# Main_schematic.net
KiCad netlist of a schematic drawn in EAGLE
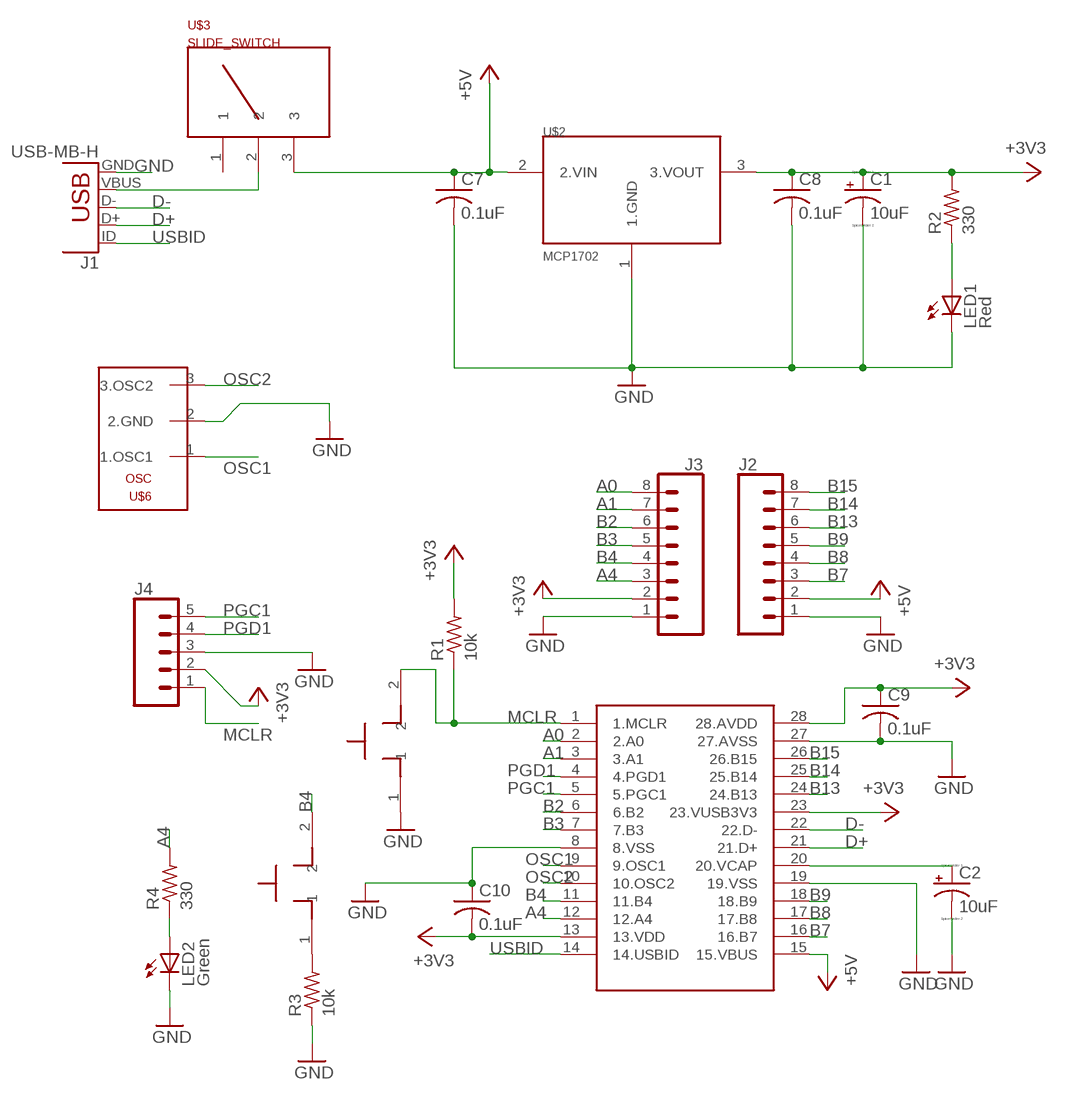
[diagram p0: schematic, sheet 1]

(export (version "E")
  (design (tool "Eeschema 10.0.6"))
  (components
    (comp (ref "C1")
      (value "10uF")
      (footprint "eagle-import:B45181B")
      (libsource (lib "eagle-import") (part "CPOL-USB45181B"))
    )
    (comp (ref "C2")
      (value "10uF")
      (footprint "eagle-import:B45181B")
      (libsource (lib "eagle-import") (part "CPOL-USB45181B"))
    )
    (comp (ref "C7")
      (value "0.1uF")
      (footprint "eagle-import:C025-024X044")
      (libsource (lib "eagle-import") (part "C-US025-024X044"))
    )
    (comp (ref "C8")
      (value "0.1uF")
      (footprint "eagle-import:C025-024X044")
      (libsource (lib "eagle-import") (part "C-US025-024X044"))
    )
    (comp (ref "C9")
      (value "0.1uF")
      (footprint "eagle-import:C025-024X044")
      (libsource (lib "eagle-import") (part "C-US025-024X044"))
    )
    (comp (ref "C10")
      (value "0.1uF")
      (footprint "eagle-import:C025-024X044")
      (libsource (lib "eagle-import") (part "C-US025-024X044"))
    )
    (comp (ref "J1")
      (value "USB-MB-H")
      (footprint "eagle-import:USB-MB-H")
      (libsource (lib "eagle-import") (part "USB-MB-H"))
    )
    (comp (ref "J2")
      (value "CONN_08\"")
      (footprint "eagle-import:1X08")
      (libsource (lib "eagle-import") (part "CONN_08{dblquote}"))
    )
    (comp (ref "J3")
      (value "CONN_08\"")
      (footprint "eagle-import:1X08")
      (libsource (lib "eagle-import") (part "CONN_08{dblquote}"))
    )
    (comp (ref "J4")
      (value "CONN_05")
      (footprint "eagle-import:1X05")
      (libsource (lib "eagle-import") (part "CONN_05"))
    )
    (comp (ref "LED1")
      (value "Red")
      (footprint "eagle-import:LED3MM")
      (libsource (lib "eagle-import") (part "LED3MM"))
    )
    (comp (ref "LED2")
      (value "Green")
      (footprint "eagle-import:LED3MM")
      (libsource (lib "eagle-import") (part "LED3MM"))
    )
    (comp (ref "R1")
      (value "10k")
      (footprint "eagle-import:0207_10")
      (libsource (lib "eagle-import") (part "R-US_0207/10"))
    )
    (comp (ref "R2")
      (value "330")
      (footprint "eagle-import:0207_10")
      (libsource (lib "eagle-import") (part "R-US_0207/10"))
    )
    (comp (ref "R3")
      (value "10k")
      (footprint "eagle-import:0207_10")
      (libsource (lib "eagle-import") (part "R-US_0207/10"))
    )
    (comp (ref "R4")
      (value "330")
      (footprint "eagle-import:0207_10")
      (libsource (lib "eagle-import") (part "R-US_0207/10"))
    )
    (comp (ref "U$1")
      (value "PIC32MX250F128B")
      (footprint "eagle-import:DIL28-3")
      (libsource (lib "eagle-import") (part "PIC32MX250F128B"))
    )
    (comp (ref "U$2")
      (value "MCP1702")
      (footprint "eagle-import:TO92")
      (libsource (lib "eagle-import") (part "MCP1702"))
    )
    (comp (ref "U$3")
      (value "SLIDE_SWITCH")
      (footprint "eagle-import:SLIDE_SWITCH")
      (libsource (lib "eagle-import") (part "SLIDE_SWITCH"))
    )
    (comp (ref "U$4") (value "PB") (footprint "eagle-import:PB") (libsource (lib "eagle-import") (part "PB")))
    (comp (ref "U$5") (value "PB") (footprint "eagle-import:PB") (libsource (lib "eagle-import") (part "PB")))
    (comp (ref "U$6")
      (value "OSC")
      (footprint "eagle-import:OSC")
      (libsource (lib "eagle-import") (part "OSC"))
    )
  )
  (nets
    (net (code "1") (name "+3V3") (class "Default")
      (node (ref "C1") (pin "+") (pinfunction "+_+") (pintype "passive"))
      (node (ref "C10") (pin "2") (pinfunction "2_2") (pintype "passive"))
      (node (ref "C8") (pin "1") (pinfunction "1_1") (pintype "passive"))
      (node (ref "C9") (pin "1") (pinfunction "1_1") (pintype "passive"))
      (node (ref "J3") (pin "2") (pinfunction "2_2") (pintype "passive"))
      (node (ref "J4") (pin "2") (pinfunction "2_2") (pintype "passive"))
      (node (ref "R1") (pin "2") (pinfunction "2_2") (pintype "passive"))
      (node (ref "R2") (pin "2") (pinfunction "2_2") (pintype "passive"))
      (node (ref "U$1") (pin "13") (pinfunction "13.VDD_13") (pintype "bidirectional"))
      (node (ref "U$1") (pin "23") (pinfunction "23.VUSB3V3_23") (pintype "bidirectional"))
      (node (ref "U$1") (pin "28") (pinfunction "28.AVDD_28") (pintype "bidirectional"))
      (node (ref "U$2") (pin "3") (pinfunction "3.VOUT_3") (pintype "bidirectional"))
    )
    (net (code "2") (name "+5V") (class "Default")
      (node (ref "C7") (pin "1") (pinfunction "1_1") (pintype "passive"))
      (node (ref "J2") (pin "2") (pinfunction "2_2") (pintype "passive"))
      (node (ref "U$1") (pin "15") (pinfunction "15.VBUS_15") (pintype "bidirectional"))
      (node (ref "U$2") (pin "2") (pinfunction "2.VIN_2") (pintype "bidirectional"))
      (node (ref "U$3") (pin "3") (pinfunction "3_3") (pintype "bidirectional"))
    )
    (net (code "3") (name "/A0") (class "Default")
      (node (ref "J3") (pin "8") (pinfunction "8_8") (pintype "passive"))
      (node (ref "U$1") (pin "2") (pinfunction "2.A0_2") (pintype "bidirectional"))
    )
    (net (code "4") (name "/A1") (class "Default")
      (node (ref "J3") (pin "7") (pinfunction "7_7") (pintype "passive"))
      (node (ref "U$1") (pin "3") (pinfunction "3.A1_3") (pintype "bidirectional"))
    )
    (net (code "5") (name "/A4") (class "Default")
      (node (ref "J3") (pin "3") (pinfunction "3_3") (pintype "passive"))
      (node (ref "R4") (pin "2") (pinfunction "2_2") (pintype "passive"))
      (node (ref "U$1") (pin "12") (pinfunction "12.A4_12") (pintype "bidirectional"))
    )
    (net (code "6") (name "/B2") (class "Default")
      (node (ref "J3") (pin "6") (pinfunction "6_6") (pintype "passive"))
      (node (ref "U$1") (pin "6") (pinfunction "6.B2_6") (pintype "bidirectional"))
    )
    (net (code "7") (name "/B3") (class "Default")
      (node (ref "J3") (pin "5") (pinfunction "5_5") (pintype "passive"))
      (node (ref "U$1") (pin "7") (pinfunction "7.B3_7") (pintype "bidirectional"))
    )
    (net (code "8") (name "/B4") (class "Default")
      (node (ref "J3") (pin "4") (pinfunction "4_4") (pintype "passive"))
      (node (ref "U$1") (pin "11") (pinfunction "11.B4_11") (pintype "bidirectional"))
      (node (ref "U$5") (pin "2") (pinfunction "2_2") (pintype "bidirectional"))
    )
    (net (code "9") (name "/B7") (class "Default")
      (node (ref "J2") (pin "3") (pinfunction "3_3") (pintype "passive"))
      (node (ref "U$1") (pin "16") (pinfunction "16.B7_16") (pintype "bidirectional"))
    )
    (net (code "10") (name "/B8") (class "Default")
      (node (ref "J2") (pin "4") (pinfunction "4_4") (pintype "passive"))
      (node (ref "U$1") (pin "17") (pinfunction "17.B8_17") (pintype "bidirectional"))
    )
    (net (code "11") (name "/B9") (class "Default")
      (node (ref "J2") (pin "5") (pinfunction "5_5") (pintype "passive"))
      (node (ref "U$1") (pin "18") (pinfunction "18.B9_18") (pintype "bidirectional"))
    )
    (net (code "12") (name "/B13") (class "Default")
      (node (ref "J2") (pin "6") (pinfunction "6_6") (pintype "passive"))
      (node (ref "U$1") (pin "24") (pinfunction "24.B13_24") (pintype "bidirectional"))
    )
    (net (code "13") (name "/B14") (class "Default")
      (node (ref "J2") (pin "7") (pinfunction "7_7") (pintype "passive"))
      (node (ref "U$1") (pin "25") (pinfunction "25.B14_25") (pintype "bidirectional"))
    )
    (net (code "14") (name "/B15") (class "Default")
      (node (ref "J2") (pin "8") (pinfunction "8_8") (pintype "passive"))
      (node (ref "U$1") (pin "26") (pinfunction "26.B15_26") (pintype "bidirectional"))
    )
    (net (code "15") (name "/D+") (class "Default")
      (node (ref "J1") (pin "D+") (pinfunction "D+_D+") (pintype "bidirectional"))
      (node (ref "U$1") (pin "21") (pinfunction "21.D+_21") (pintype "bidirectional"))
    )
    (net (code "16") (name "/D-") (class "Default")
      (node (ref "J1") (pin "D-") (pinfunction "D-_D-") (pintype "bidirectional"))
      (node (ref "U$1") (pin "22") (pinfunction "22.D-_22") (pintype "bidirectional"))
    )
    (net (code "17") (name "/MCLR") (class "Default")
      (node (ref "J4") (pin "1") (pinfunction "1_1") (pintype "passive"))
      (node (ref "R1") (pin "1") (pinfunction "1_1") (pintype "passive"))
      (node (ref "U$1") (pin "1") (pinfunction "1.MCLR_1") (pintype "bidirectional"))
      (node (ref "U$4") (pin "2") (pinfunction "2_2") (pintype "bidirectional"))
    )
    (net (code "18") (name "/OSC1") (class "Default")
      (node (ref "U$1") (pin "9") (pinfunction "9.OSC1_9") (pintype "bidirectional"))
      (node (ref "U$6") (pin "1") (pinfunction "1.OSC1_1") (pintype "bidirectional"))
    )
    (net (code "19") (name "/OSC2") (class "Default")
      (node (ref "U$1") (pin "10") (pinfunction "10.OSC2_10") (pintype "bidirectional"))
      (node (ref "U$6") (pin "3") (pinfunction "3.OSC2_3") (pintype "bidirectional"))
    )
    (net (code "20") (name "/PGC1") (class "Default")
      (node (ref "J4") (pin "5") (pinfunction "5_5") (pintype "passive"))
      (node (ref "U$1") (pin "5") (pinfunction "5.PGC1_5") (pintype "bidirectional"))
    )
    (net (code "21") (name "/PGD1") (class "Default")
      (node (ref "J4") (pin "4") (pinfunction "4_4") (pintype "passive"))
      (node (ref "U$1") (pin "4") (pinfunction "4.PGD1_4") (pintype "bidirectional"))
    )
    (net (code "22") (name "/USBID") (class "Default")
      (node (ref "J1") (pin "ID") (pinfunction "ID_ID") (pintype "bidirectional"))
      (node (ref "U$1") (pin "14") (pinfunction "14.USBID_14") (pintype "bidirectional"))
    )
    (net (code "23") (name "GND") (class "Default")
      (node (ref "C1") (pin "-") (pinfunction "-_-") (pintype "passive"))
      (node (ref "C10") (pin "1") (pinfunction "1_1") (pintype "passive"))
      (node (ref "C2") (pin "-") (pinfunction "-_-") (pintype "passive"))
      (node (ref "C7") (pin "2") (pinfunction "2_2") (pintype "passive"))
      (node (ref "C8") (pin "2") (pinfunction "2_2") (pintype "passive"))
      (node (ref "C9") (pin "2") (pinfunction "2_2") (pintype "passive"))
      (node (ref "J1") (pin "GND") (pinfunction "GND_GND") (pintype "bidirectional"))
      (node (ref "J2") (pin "1") (pinfunction "1_1") (pintype "passive"))
      (node (ref "J3") (pin "1") (pinfunction "1_1") (pintype "passive"))
      (node (ref "J4") (pin "3") (pinfunction "3_3") (pintype "passive"))
      (node (ref "LED1") (pin "K") (pinfunction "C_K") (pintype "passive"))
      (node (ref "LED2") (pin "K") (pinfunction "C_K") (pintype "passive"))
      (node (ref "R3") (pin "1") (pinfunction "1_1") (pintype "passive"))
      (node (ref "U$1") (pin "19") (pinfunction "19.VSS_19") (pintype "bidirectional"))
      (node (ref "U$1") (pin "27") (pinfunction "27.AVSS_27") (pintype "bidirectional"))
      (node (ref "U$1") (pin "8") (pinfunction "8.VSS_8") (pintype "bidirectional"))
      (node (ref "U$2") (pin "1") (pinfunction "1.GND_1") (pintype "bidirectional"))
      (node (ref "U$4") (pin "1") (pinfunction "1_1") (pintype "bidirectional"))
      (node (ref "U$6") (pin "2") (pinfunction "2.GND_2") (pintype "bidirectional"))
    )
    (net (code "24") (name "Net-(J1-PadVBUS)") (class "Default")
      (node (ref "J1") (pin "VBUS") (pinfunction "VBUS_VBUS") (pintype "bidirectional"))
      (node (ref "U$3") (pin "2") (pinfunction "2_2") (pintype "bidirectional"))
    )
    (net (code "25") (name "Net-(LED1-PadA)") (class "Default")
      (node (ref "LED1") (pin "A") (pinfunction "A_A") (pintype "passive"))
      (node (ref "R2") (pin "1") (pinfunction "1_1") (pintype "passive"))
    )
    (net (code "26") (name "Net-(LED2-PadA)") (class "Default")
      (node (ref "LED2") (pin "A") (pinfunction "A_A") (pintype "passive"))
      (node (ref "R4") (pin "1") (pinfunction "1_1") (pintype "passive"))
    )
    (net (code "27") (name "Net-(R3-Pad2)") (class "Default")
      (node (ref "R3") (pin "2") (pinfunction "2_2") (pintype "passive"))
      (node (ref "U$5") (pin "1") (pinfunction "1_1") (pintype "bidirectional"))
    )
    (net (code "28") (name "Net-(U$1-20.VCAP)") (class "Default")
      (node (ref "C2") (pin "+") (pinfunction "+_+") (pintype "passive"))
      (node (ref "U$1") (pin "20") (pinfunction "20.VCAP_20") (pintype "bidirectional"))
    )
    (net (code "29") (name "unconnected-(U$3-Pad1)") (class "Default")
      (node (ref "U$3") (pin "1") (pinfunction "1_1") (pintype "bidirectional"))
    )
  )
)
